# SCH_Endurance_drone_7.net
KiCad netlist of a schematic drawn in EasyEDA
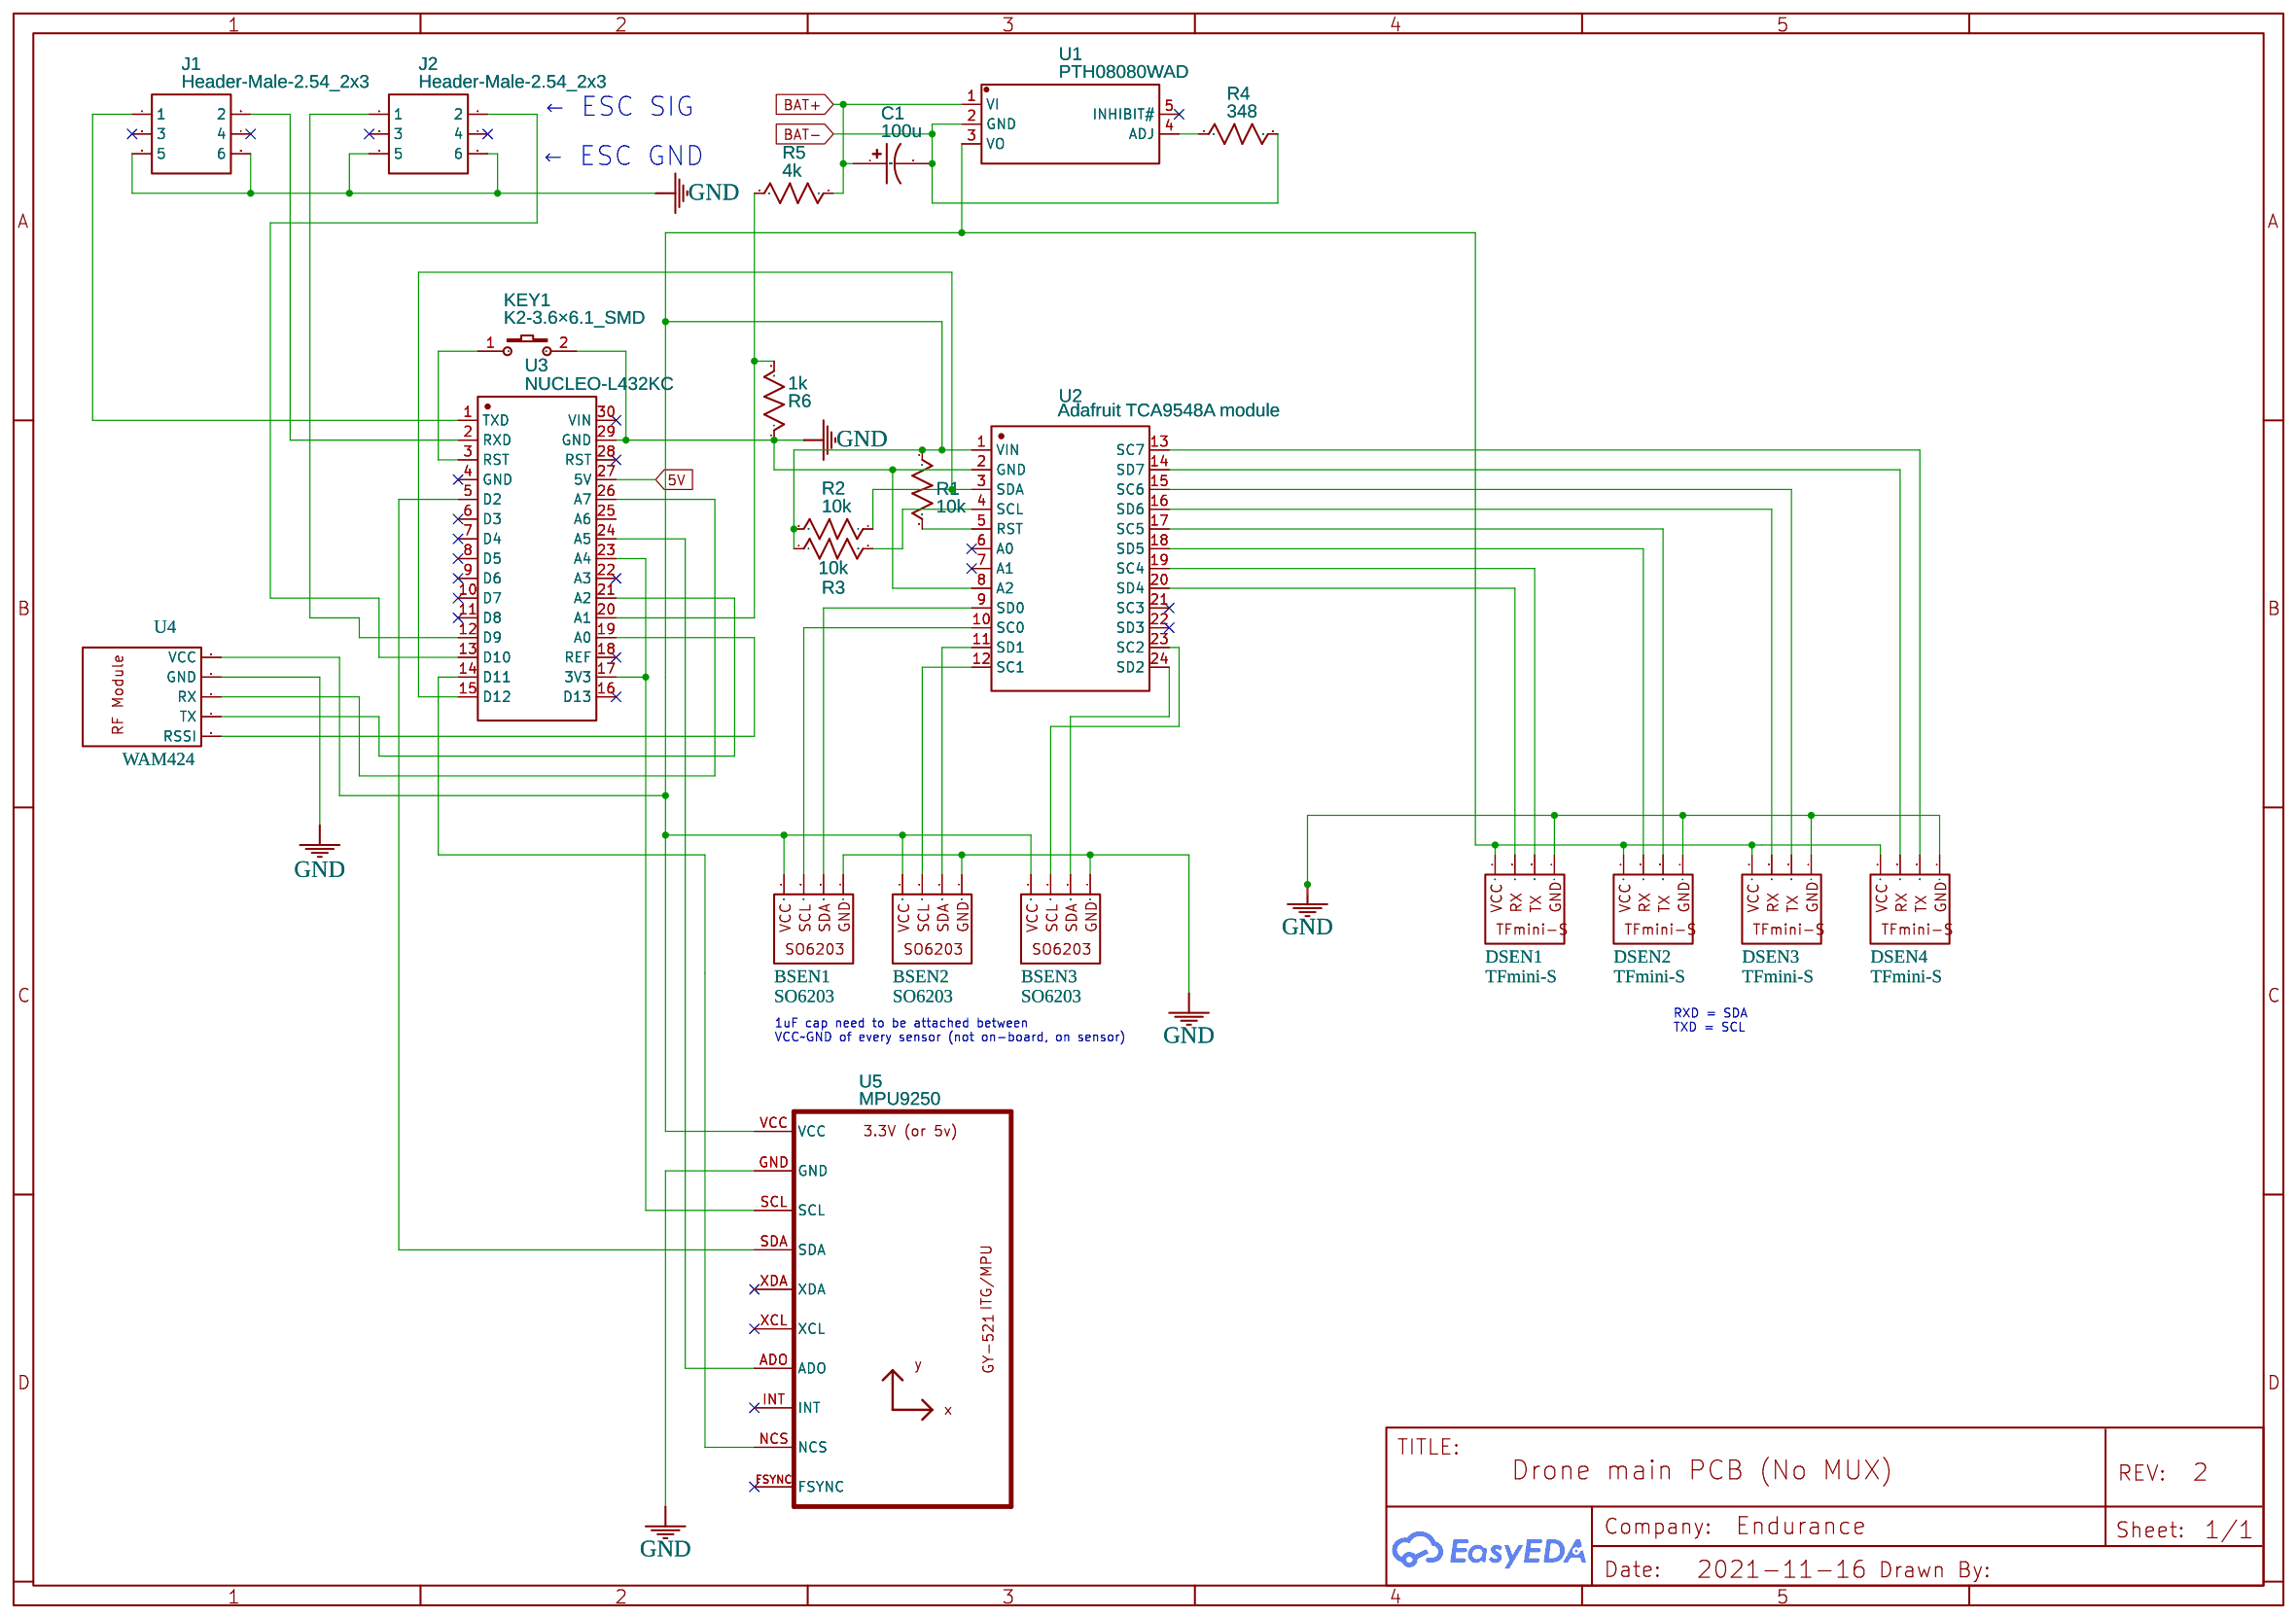
[diagram p0: schematic sheet]

(export (version "E")
  (design (tool "Eeschema 10.0.6"))
  (components
    (comp (ref "BSEN1") (value "SO6203") (libsource (lib "") (part "Unknown_405_-350")))
    (comp (ref "BSEN2") (value "SO6203") (libsource (lib "") (part "Unknown_465_-350")))
    (comp (ref "BSEN3") (value "SO6203") (libsource (lib "") (part "Unknown_530_-350")))
    (comp (ref "C1") (value "100u") (libsource (lib "") (part "C_Tan_SMD_A_US")))
    (comp (ref "DSEN1") (value "TFmini-S") (libsource (lib "") (part "Unknown_765_-360")))
    (comp (ref "DSEN2") (value "TFmini-S") (libsource (lib "") (part "Unknown_830_-360")))
    (comp (ref "DSEN3") (value "TFmini-S") (libsource (lib "") (part "Unknown_895_-360")))
    (comp (ref "DSEN4") (value "TFmini-S") (libsource (lib "") (part "Unknown_960_-360")))
    (comp (ref "J1")
      (value "Header-Male-2.54_2x3")
      (fields (field (name "BOM_Supplier Part") "C65114"))
      (libsource (lib "") (part "Header-Male-2.54_2x3"))
    )
    (comp (ref "J2")
      (value "Header-Male-2.54_2x3")
      (fields (field (name "BOM_Supplier Part") "C65114"))
      (libsource (lib "") (part "Header-Male-2.54_2x3"))
    )
    (comp (ref "KEY1")
      (value "K2-3.6×6.1_SMD")
      (fields
        (field (name "BOM_Manufacturer Part") "K2-1107ST-A4SW-06")
        (field (name "BOM_Supplier Part") "C118141")
      )
      (libsource (lib "") (part "K2-3.6×6.1_SMD"))
    )
    (comp (ref "R1") (value "10k") (libsource (lib "") (part "R_0603_US_1")))
    (comp (ref "R2") (value "10k") (libsource (lib "") (part "R_0603_US_3")))
    (comp (ref "R3") (value "10k") (libsource (lib "") (part "R_0603_US_2")))
    (comp (ref "R4") (value "348") (libsource (lib "") (part "R_0603_US_2")))
    (comp (ref "R5") (value "4k") (libsource (lib "") (part "R_0603_US_3")))
    (comp (ref "R6") (value "1k") (libsource (lib "") (part "R_0603_US")))
    (comp (ref "U1")
      (value "PTH08080WAD")
      (fields (field (name "BOM_Supplier Part") "C154927"))
      (libsource (lib "") (part "PTH08080WAD"))
    )
    (comp (ref "U2")
      (value "Adafruit TCA9548A module")
      (fields
        (field (name "BOM_Manufacturer Part") "TCA9548APWR")
        (field (name "BOM_Supplier Part") "C130026")
      )
      (libsource (lib "") (part "TCA9548APWR"))
    )
    (comp (ref "U3")
      (value "NUCLEO-L432KC")
      (fields (field (name "BOM_Supplier Part") "C94814"))
      (libsource (lib "") (part "NUCLEO-L432KC"))
    )
    (comp (ref "U4") (value "WAM424") (libsource (lib "") (part "Unknown_70_-460")))
    (comp (ref "U5") (value "MPU9250") (libsource (lib "") (part "MPU9250")))
  )
  (nets
    (net (code "1") (name "5V") (class "Default")
      (node (ref "U3") (pin "27") (pinfunction "5V_27") (pintype "unspecified"))
    )
    (net (code "2") (name "BAT+") (class "Default")
      (node (ref "C1") (pin "1") (pinfunction "1_1") (pintype "unspecified"))
      (node (ref "R5") (pin "1") (pinfunction "1_1") (pintype "unspecified"))
      (node (ref "U1") (pin "1") (pinfunction "VI_1") (pintype "unspecified"))
    )
    (net (code "3") (name "BAT-") (class "Default")
      (node (ref "C1") (pin "2") (pinfunction "2_2") (pintype "unspecified"))
      (node (ref "R4") (pin "2") (pinfunction "2_2") (pintype "unspecified"))
      (node (ref "U1") (pin "2") (pinfunction "GND_2") (pintype "unspecified"))
    )
    (net (code "4") (name "GND") (class "Default")
      (node (ref "BSEN1") (pin "4") (pinfunction "4_4") (pintype "unspecified"))
      (node (ref "BSEN2") (pin "4") (pinfunction "4_4") (pintype "unspecified"))
      (node (ref "BSEN3") (pin "4") (pinfunction "4_4") (pintype "unspecified"))
      (node (ref "DSEN1") (pin "4") (pinfunction "4_4") (pintype "unspecified"))
      (node (ref "DSEN2") (pin "4") (pinfunction "4_4") (pintype "unspecified"))
      (node (ref "DSEN3") (pin "4") (pinfunction "4_4") (pintype "unspecified"))
      (node (ref "DSEN4") (pin "4") (pinfunction "4_4") (pintype "unspecified"))
      (node (ref "J1") (pin "5") (pinfunction "5_5") (pintype "input"))
      (node (ref "J1") (pin "6") (pinfunction "6_6") (pintype "input"))
      (node (ref "J2") (pin "5") (pinfunction "5_5") (pintype "input"))
      (node (ref "J2") (pin "6") (pinfunction "6_6") (pintype "input"))
      (node (ref "KEY1") (pin "2") (pinfunction "2_2") (pintype "unspecified"))
      (node (ref "R6") (pin "1") (pinfunction "1_1") (pintype "unspecified"))
      (node (ref "U2") (pin "2") (pinfunction "GND_2") (pintype "unspecified"))
      (node (ref "U2") (pin "8") (pinfunction "A2_8") (pintype "unspecified"))
      (node (ref "U3") (pin "29") (pinfunction "GND_29") (pintype "unspecified"))
      (node (ref "U4") (pin "2") (pinfunction "GND_2") (pintype "unspecified"))
      (node (ref "U5") (pin "GND") (pinfunction "GND_GND") (pintype "bidirectional"))
    )
    (net (code "5") (name "Net-(KEY1-Pad1)") (class "Default")
      (node (ref "KEY1") (pin "1") (pinfunction "1_1") (pintype "unspecified"))
      (node (ref "U3") (pin "3") (pinfunction "RST_3") (pintype "unspecified"))
    )
    (net (code "6") (name "Net-(U1-ADJ)") (class "Default")
      (node (ref "R4") (pin "1") (pinfunction "1_1") (pintype "unspecified"))
      (node (ref "U1") (pin "4") (pinfunction "ADJ_4") (pintype "unspecified"))
    )
    (net (code "7") (name "Net-(U1-VO)") (class "Default")
      (node (ref "BSEN1") (pin "1") (pinfunction "1_1") (pintype "unspecified"))
      (node (ref "BSEN2") (pin "1") (pinfunction "1_1") (pintype "unspecified"))
      (node (ref "BSEN3") (pin "1") (pinfunction "1_1") (pintype "unspecified"))
      (node (ref "DSEN1") (pin "1") (pinfunction "1_1") (pintype "unspecified"))
      (node (ref "DSEN2") (pin "1") (pinfunction "1_1") (pintype "unspecified"))
      (node (ref "DSEN3") (pin "1") (pinfunction "1_1") (pintype "unspecified"))
      (node (ref "DSEN4") (pin "1") (pinfunction "1_1") (pintype "unspecified"))
      (node (ref "R1") (pin "1") (pinfunction "1_1") (pintype "unspecified"))
      (node (ref "R2") (pin "2") (pinfunction "2_2") (pintype "unspecified"))
      (node (ref "R3") (pin "1") (pinfunction "1_1") (pintype "unspecified"))
      (node (ref "U1") (pin "3") (pinfunction "VO_3") (pintype "unspecified"))
      (node (ref "U2") (pin "1") (pinfunction "VIN_1") (pintype "unspecified"))
      (node (ref "U4") (pin "1") (pinfunction "VCC_1") (pintype "unspecified"))
      (node (ref "U5") (pin "VCC") (pinfunction "VCC_VCC") (pintype "bidirectional"))
    )
    (net (code "8") (name "Net-(U2-RST)") (class "Default")
      (node (ref "R1") (pin "2") (pinfunction "2_2") (pintype "unspecified"))
      (node (ref "U2") (pin "5") (pinfunction "RST_5") (pintype "unspecified"))
    )
    (net (code "9") (name "Net-(U2-SC0)") (class "Default")
      (node (ref "BSEN1") (pin "2") (pinfunction "2_2") (pintype "unspecified"))
      (node (ref "U2") (pin "10") (pinfunction "SC0_10") (pintype "unspecified"))
    )
    (net (code "10") (name "Net-(U2-SC1)") (class "Default")
      (node (ref "BSEN2") (pin "2") (pinfunction "2_2") (pintype "unspecified"))
      (node (ref "U2") (pin "12") (pinfunction "SC1_12") (pintype "unspecified"))
    )
    (net (code "11") (name "Net-(U2-SC2)") (class "Default")
      (node (ref "BSEN3") (pin "2") (pinfunction "2_2") (pintype "unspecified"))
      (node (ref "U2") (pin "23") (pinfunction "SC2_23") (pintype "unspecified"))
    )
    (net (code "12") (name "Net-(U2-SC4)") (class "Default")
      (node (ref "DSEN1") (pin "3") (pinfunction "3_3") (pintype "unspecified"))
      (node (ref "U2") (pin "19") (pinfunction "SC4_19") (pintype "unspecified"))
    )
    (net (code "13") (name "Net-(U2-SC5)") (class "Default")
      (node (ref "DSEN2") (pin "3") (pinfunction "3_3") (pintype "unspecified"))
      (node (ref "U2") (pin "17") (pinfunction "SC5_17") (pintype "unspecified"))
    )
    (net (code "14") (name "Net-(U2-SC6)") (class "Default")
      (node (ref "DSEN3") (pin "3") (pinfunction "3_3") (pintype "unspecified"))
      (node (ref "U2") (pin "15") (pinfunction "SC6_15") (pintype "unspecified"))
    )
    (net (code "15") (name "Net-(U2-SC7)") (class "Default")
      (node (ref "DSEN4") (pin "3") (pinfunction "3_3") (pintype "unspecified"))
      (node (ref "U2") (pin "13") (pinfunction "SC7_13") (pintype "unspecified"))
    )
    (net (code "16") (name "Net-(U2-SCL)") (class "Default")
      (node (ref "R3") (pin "2") (pinfunction "2_2") (pintype "unspecified"))
      (node (ref "U2") (pin "4") (pinfunction "SCL_4") (pintype "unspecified"))
    )
    (net (code "17") (name "Net-(U2-SD0)") (class "Default")
      (node (ref "BSEN1") (pin "3") (pinfunction "3_3") (pintype "unspecified"))
      (node (ref "U2") (pin "9") (pinfunction "SD0_9") (pintype "unspecified"))
    )
    (net (code "18") (name "Net-(U2-SD1)") (class "Default")
      (node (ref "BSEN2") (pin "3") (pinfunction "3_3") (pintype "unspecified"))
      (node (ref "U2") (pin "11") (pinfunction "SD1_11") (pintype "unspecified"))
    )
    (net (code "19") (name "Net-(U2-SD2)") (class "Default")
      (node (ref "BSEN3") (pin "3") (pinfunction "3_3") (pintype "unspecified"))
      (node (ref "U2") (pin "24") (pinfunction "SD2_24") (pintype "unspecified"))
    )
    (net (code "20") (name "Net-(U2-SD4)") (class "Default")
      (node (ref "DSEN1") (pin "2") (pinfunction "2_2") (pintype "unspecified"))
      (node (ref "U2") (pin "20") (pinfunction "SD4_20") (pintype "unspecified"))
    )
    (net (code "21") (name "Net-(U2-SD5)") (class "Default")
      (node (ref "DSEN2") (pin "2") (pinfunction "2_2") (pintype "unspecified"))
      (node (ref "U2") (pin "18") (pinfunction "SD5_18") (pintype "unspecified"))
    )
    (net (code "22") (name "Net-(U2-SD6)") (class "Default")
      (node (ref "DSEN3") (pin "2") (pinfunction "2_2") (pintype "unspecified"))
      (node (ref "U2") (pin "16") (pinfunction "SD6_16") (pintype "unspecified"))
    )
    (net (code "23") (name "Net-(U2-SD7)") (class "Default")
      (node (ref "DSEN4") (pin "2") (pinfunction "2_2") (pintype "unspecified"))
      (node (ref "U2") (pin "14") (pinfunction "SD7_14") (pintype "unspecified"))
    )
    (net (code "24") (name "Net-(U2-SDA)") (class "Default")
      (node (ref "R2") (pin "1") (pinfunction "1_1") (pintype "unspecified"))
      (node (ref "U2") (pin "3") (pinfunction "SDA_3") (pintype "unspecified"))
      (node (ref "U3") (pin "15") (pinfunction "D12_15") (pintype "unspecified"))
    )
    (net (code "25") (name "Net-(U3-3V3)") (class "Default")
      (node (ref "U3") (pin "17") (pinfunction "3V3_17") (pintype "unspecified"))
      (node (ref "U3") (pin "23") (pinfunction "A4_23") (pintype "unspecified"))
      (node (ref "U5") (pin "SCL") (pinfunction "SCL_SCL") (pintype "bidirectional"))
    )
    (net (code "26") (name "Net-(U3-A0)") (class "Default")
      (node (ref "U3") (pin "19") (pinfunction "A0_19") (pintype "unspecified"))
      (node (ref "U4") (pin "5") (pinfunction "RSSI_5") (pintype "unspecified"))
    )
    (net (code "27") (name "Net-(U3-A1)") (class "Default")
      (node (ref "R5") (pin "2") (pinfunction "2_2") (pintype "unspecified"))
      (node (ref "R6") (pin "2") (pinfunction "2_2") (pintype "unspecified"))
      (node (ref "U3") (pin "20") (pinfunction "A1_20") (pintype "unspecified"))
    )
    (net (code "28") (name "Net-(U3-A2)") (class "Default")
      (node (ref "U3") (pin "21") (pinfunction "A2_21") (pintype "unspecified"))
      (node (ref "U4") (pin "4") (pinfunction "TX_4") (pintype "unspecified"))
    )
    (net (code "29") (name "Net-(U3-A5)") (class "Default")
      (node (ref "U3") (pin "24") (pinfunction "A5_24") (pintype "unspecified"))
      (node (ref "U5") (pin "ADO") (pinfunction "ADO_ADO") (pintype "bidirectional"))
    )
    (net (code "30") (name "Net-(U3-A7)") (class "Default")
      (node (ref "U3") (pin "26") (pinfunction "A7_26") (pintype "unspecified"))
      (node (ref "U4") (pin "3") (pinfunction "RX_3") (pintype "unspecified"))
    )
    (net (code "31") (name "Net-(U3-D2)") (class "Default")
      (node (ref "U3") (pin "5") (pinfunction "D2_5") (pintype "unspecified"))
      (node (ref "U5") (pin "SDA") (pinfunction "SDA_SDA") (pintype "bidirectional"))
    )
    (net (code "32") (name "Net-(U3-D9)") (class "Default")
      (node (ref "J2") (pin "1") (pinfunction "1_1") (pintype "input"))
      (node (ref "U3") (pin "12") (pinfunction "D9_12") (pintype "unspecified"))
    )
    (net (code "33") (name "Net-(U3-D10)") (class "Default")
      (node (ref "J2") (pin "2") (pinfunction "2_2") (pintype "input"))
      (node (ref "U3") (pin "13") (pinfunction "D10_13") (pintype "unspecified"))
    )
    (net (code "34") (name "Net-(U3-D11)") (class "Default")
      (node (ref "U3") (pin "14") (pinfunction "D11_14") (pintype "unspecified"))
      (node (ref "U5") (pin "NCS") (pinfunction "NCS_NCS") (pintype "bidirectional"))
    )
    (net (code "35") (name "Net-(U3-RXD)") (class "Default")
      (node (ref "J1") (pin "2") (pinfunction "2_2") (pintype "input"))
      (node (ref "U3") (pin "2") (pinfunction "RXD_2") (pintype "unspecified"))
    )
    (net (code "36") (name "Net-(U3-TXD)") (class "Default")
      (node (ref "J1") (pin "1") (pinfunction "1_1") (pintype "input"))
      (node (ref "U3") (pin "1") (pinfunction "TXD_1") (pintype "unspecified"))
    )
    (net (code "37") (name "unconnected-(J1-Pad3)") (class "Default")
      (node (ref "J1") (pin "3") (pinfunction "3_3") (pintype "input+no_connect"))
    )
    (net (code "38") (name "unconnected-(J1-Pad4)") (class "Default")
      (node (ref "J1") (pin "4") (pinfunction "4_4") (pintype "input+no_connect"))
    )
    (net (code "39") (name "unconnected-(J2-Pad3)") (class "Default")
      (node (ref "J2") (pin "3") (pinfunction "3_3") (pintype "input+no_connect"))
    )
    (net (code "40") (name "unconnected-(J2-Pad4)") (class "Default")
      (node (ref "J2") (pin "4") (pinfunction "4_4") (pintype "input+no_connect"))
    )
    (net (code "41") (name "unconnected-(U1-INHIBIT#-Pad5)") (class "Default")
      (node (ref "U1") (pin "5") (pinfunction "INHIBIT#_5") (pintype "unspecified+no_connect"))
    )
    (net (code "42") (name "unconnected-(U2-A0-Pad6)") (class "Default")
      (node (ref "U2") (pin "6") (pinfunction "A0_6") (pintype "unspecified+no_connect"))
    )
    (net (code "43") (name "unconnected-(U2-A1-Pad7)") (class "Default")
      (node (ref "U2") (pin "7") (pinfunction "A1_7") (pintype "unspecified+no_connect"))
    )
    (net (code "44") (name "unconnected-(U2-SC3-Pad21)") (class "Default")
      (node (ref "U2") (pin "21") (pinfunction "SC3_21") (pintype "unspecified+no_connect"))
    )
    (net (code "45") (name "unconnected-(U2-SD3-Pad22)") (class "Default")
      (node (ref "U2") (pin "22") (pinfunction "SD3_22") (pintype "unspecified+no_connect"))
    )
    (net (code "46") (name "unconnected-(U3-A3-Pad22)") (class "Default")
      (node (ref "U3") (pin "22") (pinfunction "A3_22") (pintype "unspecified+no_connect"))
    )
    (net (code "47") (name "unconnected-(U3-A6-Pad25)") (class "Default")
      (node (ref "U3") (pin "25") (pinfunction "A6_25") (pintype "unspecified"))
    )
    (net (code "48") (name "unconnected-(U3-D3-Pad6)") (class "Default")
      (node (ref "U3") (pin "6") (pinfunction "D3_6") (pintype "unspecified+no_connect"))
    )
    (net (code "49") (name "unconnected-(U3-D4-Pad7)") (class "Default")
      (node (ref "U3") (pin "7") (pinfunction "D4_7") (pintype "unspecified+no_connect"))
    )
    (net (code "50") (name "unconnected-(U3-D5-Pad8)") (class "Default")
      (node (ref "U3") (pin "8") (pinfunction "D5_8") (pintype "unspecified+no_connect"))
    )
    (net (code "51") (name "unconnected-(U3-D6-Pad9)") (class "Default")
      (node (ref "U3") (pin "9") (pinfunction "D6_9") (pintype "unspecified+no_connect"))
    )
    (net (code "52") (name "unconnected-(U3-D7-Pad10)") (class "Default")
      (node (ref "U3") (pin "10") (pinfunction "D7_10") (pintype "unspecified+no_connect"))
    )
    (net (code "53") (name "unconnected-(U3-D8-Pad11)") (class "Default")
      (node (ref "U3") (pin "11") (pinfunction "D8_11") (pintype "unspecified+no_connect"))
    )
    (net (code "54") (name "unconnected-(U3-D13-Pad16)") (class "Default")
      (node (ref "U3") (pin "16") (pinfunction "D13_16") (pintype "unspecified+no_connect"))
    )
    (net (code "55") (name "unconnected-(U3-GND-Pad4)") (class "Default")
      (node (ref "U3") (pin "4") (pinfunction "GND_4") (pintype "unspecified+no_connect"))
    )
    (net (code "56") (name "unconnected-(U3-REF-Pad18)") (class "Default")
      (node (ref "U3") (pin "18") (pinfunction "REF_18") (pintype "unspecified+no_connect"))
    )
    (net (code "57") (name "unconnected-(U3-RST-Pad28)") (class "Default")
      (node (ref "U3") (pin "28") (pinfunction "RST_28") (pintype "unspecified+no_connect"))
    )
    (net (code "58") (name "unconnected-(U3-VIN-Pad30)") (class "Default")
      (node (ref "U3") (pin "30") (pinfunction "VIN_30") (pintype "unspecified+no_connect"))
    )
    (net (code "59") (name "unconnected-(U5-PadFSYNC)") (class "Default")
      (node (ref "U5") (pin "FSYNC") (pinfunction "FSYNC_FSYNC") (pintype "bidirectional+no_connect"))
    )
    (net (code "60") (name "unconnected-(U5-PadINT)") (class "Default")
      (node (ref "U5") (pin "INT") (pinfunction "INT_INT") (pintype "bidirectional+no_connect"))
    )
    (net (code "61") (name "unconnected-(U5-PadXCL)") (class "Default")
      (node (ref "U5") (pin "XCL") (pinfunction "XCL_XCL") (pintype "bidirectional+no_connect"))
    )
    (net (code "62") (name "unconnected-(U5-PadXDA)") (class "Default")
      (node (ref "U5") (pin "XDA") (pinfunction "XDA_XDA") (pintype "bidirectional+no_connect"))
    )
  )
)
